# programming.net
KiCad netlist of a schematic drawn in Altium Designer
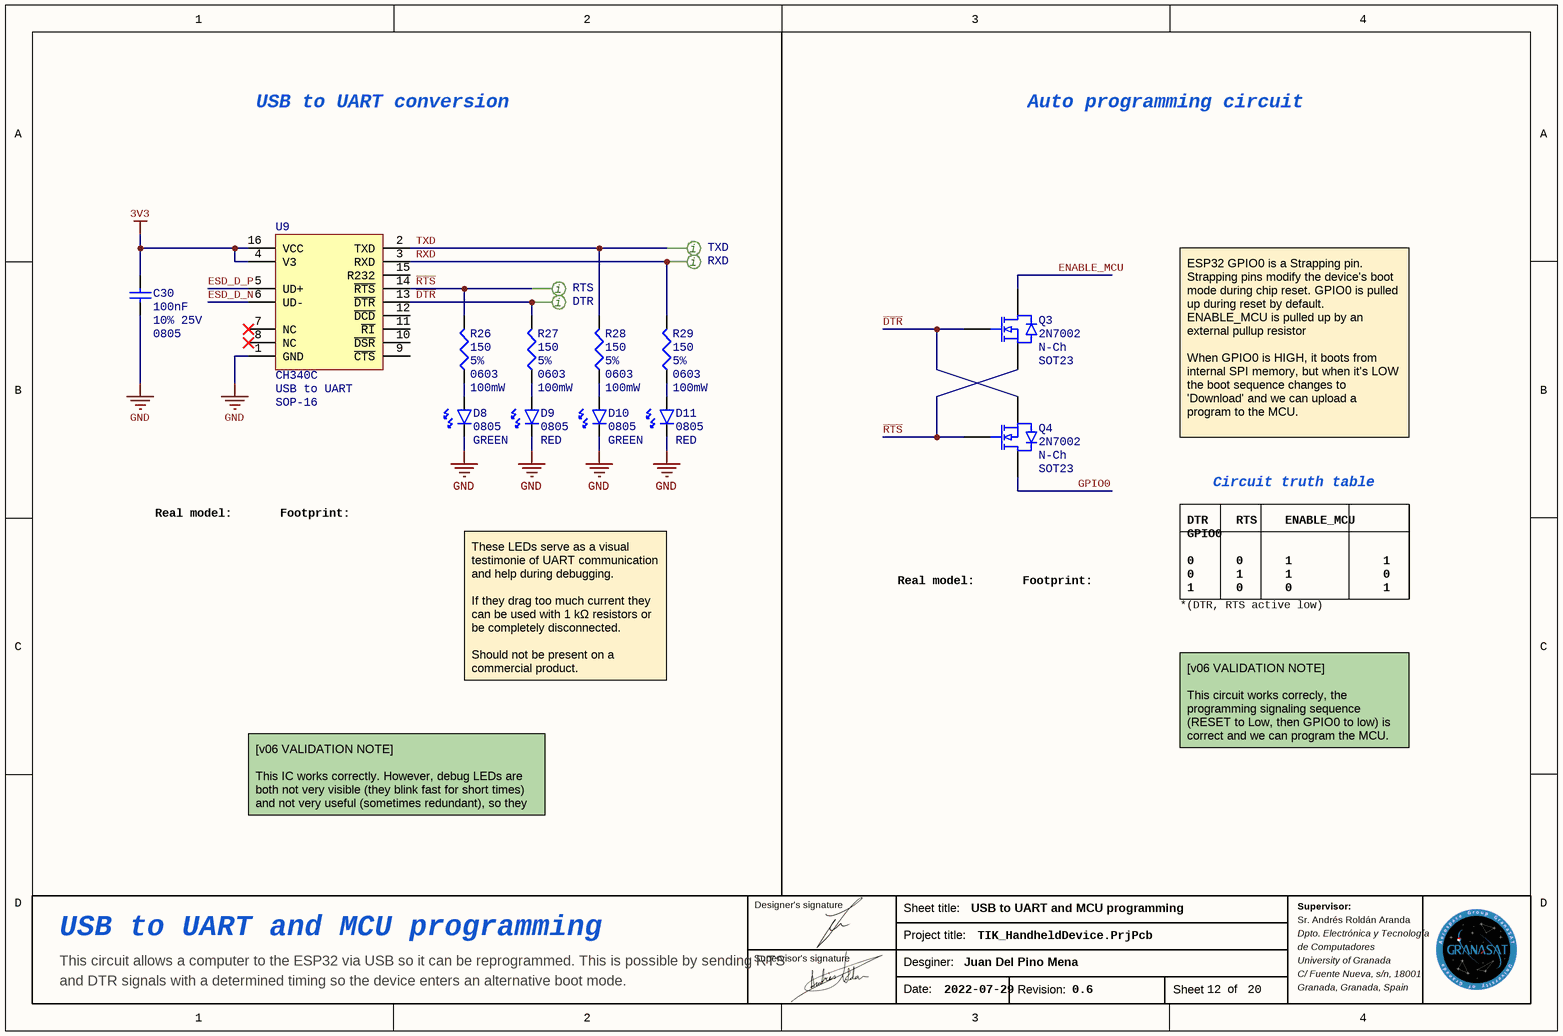
[diagram p0: programming.SchDoc]

(export (version "E")
  (design (tool "Eeschema 10.0.6"))
  (components
    (comp (ref "C30")
      (value "100nF")
      (footprint "CAP 0805_2012")
      (description "Ceramic cap size 0805")
      (fields
        (field (name "TOLERANCE") "10% 25V")
        (field (name "PACKAGEDESCRIPTION") "0805")
        (field (name "Comment") "Cap_cer_0805")
      )
      (libsource (lib "tik_handheld_schlib") (part "Cap_cer_0805_100nF_10%"))
    )
    (comp (ref "D8")
      (value "Diode LED_G_0805")
      (footprint "LED 0805_2012 GREEN")
      (description "Low power LED color Green")
      (fields (field (name "PACKAGEDESCRIPTION") "0805") (field (name "TYPE") "GREEN"))
      (libsource (lib "tik_handheld_schlib") (part "Diode LED_G_0805"))
    )
    (comp (ref "D9")
      (value "Diode LED_R_0805")
      (footprint "LED 0805_2012 RED")
      (description "Low power LED color Red")
      (fields (field (name "PACKAGEDESCRIPTION") "0805") (field (name "TYPE") "RED"))
      (libsource (lib "tik_handheld_schlib") (part "Diode LED_R_0805"))
    )
    (comp (ref "D10")
      (value "Diode LED_G_0805")
      (footprint "LED 0805_2012 GREEN")
      (description "Low power LED color Green")
      (fields (field (name "PACKAGEDESCRIPTION") "0805") (field (name "TYPE") "GREEN"))
      (libsource (lib "tik_handheld_schlib") (part "Diode LED_G_0805"))
    )
    (comp (ref "D11")
      (value "Diode LED_R_0805")
      (footprint "LED 0805_2012 RED")
      (description "Low power LED color Red")
      (fields (field (name "PACKAGEDESCRIPTION") "0805") (field (name "TYPE") "RED"))
      (libsource (lib "tik_handheld_schlib") (part "Diode LED_R_0805"))
    )
    (comp (ref "DTR")
      (value "Test Point Pad dual sided")
      (footprint "TEST POINT PAD")
      (description "Test point - PCB Pad dual sided")
      (libsource (lib "tik_handheld_schlib") (part "Test Point Pad dual sided"))
    )
    (comp (ref "Q3")
      (value "NMOS 2N7002")
      (footprint "SOT-23-3 TO-236AB 2N7002")
      (fields
        (field (name "PART") "2N7002")
        (field (name "TYPE") "N-Ch")
        (field (name "PACKAGEDESCRIPTION") "SOT23")
      )
      (libsource (lib "tik_handheld_schlib") (part "NMOS 2N7002"))
    )
    (comp (ref "Q4")
      (value "NMOS 2N7002")
      (footprint "SOT-23-3 TO-236AB 2N7002")
      (fields
        (field (name "PART") "2N7002")
        (field (name "TYPE") "N-Ch")
        (field (name "PACKAGEDESCRIPTION") "SOT23")
      )
      (libsource (lib "tik_handheld_schlib") (part "NMOS 2N7002"))
    )
    (comp (ref "R26")
      (value "150")
      (footprint "RES 0603_1608")
      (description "Res size 0603 SMD mounting, low power")
      (fields
        (field (name "TOLERANCE") "5%")
        (field (name "PACKAGEDESCRIPTION") "0603")
        (field (name "POWERDISIPATED") "100mW")
        (field (name "Comment") "Res_0603_150_5%_100mW")
      )
      (libsource (lib "tik_handheld_schlib") (part "Res_0603_150_5%_100mW"))
    )
    (comp (ref "R27")
      (value "150")
      (footprint "RES 0603_1608")
      (description "Res size 0603 SMD mounting, low power")
      (fields
        (field (name "TOLERANCE") "5%")
        (field (name "PACKAGEDESCRIPTION") "0603")
        (field (name "POWERDISIPATED") "100mW")
        (field (name "Comment") "Res_0603_150_5%_100mW")
      )
      (libsource (lib "tik_handheld_schlib") (part "Res_0603_150_5%_100mW"))
    )
    (comp (ref "R28")
      (value "150")
      (footprint "RES 0603_1608")
      (description "Res size 0603 SMD mounting, low power")
      (fields
        (field (name "TOLERANCE") "5%")
        (field (name "PACKAGEDESCRIPTION") "0603")
        (field (name "POWERDISIPATED") "100mW")
        (field (name "Comment") "Res_0603_150_5%_100mW")
      )
      (libsource (lib "tik_handheld_schlib") (part "Res_0603_150_5%_100mW"))
    )
    (comp (ref "R29")
      (value "150")
      (footprint "RES 0603_1608")
      (description "Res size 0603 SMD mounting, low power")
      (fields
        (field (name "TOLERANCE") "5%")
        (field (name "PACKAGEDESCRIPTION") "0603")
        (field (name "POWERDISIPATED") "100mW")
        (field (name "Comment") "Res_0603_150_5%_100mW")
      )
      (libsource (lib "tik_handheld_schlib") (part "Res_0603_150_5%_100mW"))
    )
    (comp (ref "RTS")
      (value "Test Point Pad dual sided")
      (footprint "TEST POINT PAD")
      (description "Test point - PCB Pad dual sided")
      (libsource (lib "tik_handheld_schlib") (part "Test Point Pad dual sided"))
    )
    (comp (ref "RXD")
      (value "Test Point Pad dual sided")
      (footprint "TEST POINT PAD")
      (description "Test point - PCB Pad dual sided")
      (libsource (lib "tik_handheld_schlib") (part "Test Point Pad dual sided"))
    )
    (comp (ref "TXD")
      (value "Test Point Pad dual sided")
      (footprint "TEST POINT PAD")
      (description "Test point - PCB Pad dual sided")
      (libsource (lib "tik_handheld_schlib") (part "Test Point Pad dual sided"))
    )
    (comp (ref "U9")
      (value "CH340C")
      (footprint "SSOP-16 150mil CH340C")
      (description "USB to serial chip CH340C, integrated oscillator.")
      (fields
        (field (name "PART") "CH340C")
        (field (name "TYPE") "USB to UART")
        (field (name "PACKAGEDESCRIPTION") "SOP-16")
      )
      (libsource (lib "tik_handheld_schlib") (part "IC CH340C usb to ttl"))
    )
  )
  (nets
    (net (code "1") (name "/ENABLE_MCU") (class "Default")
      (node (ref "Q3") (pin "3") (pinfunction "D_3") (pintype "passive"))
    )
    (net (code "2") (name "/ESD_D_N") (class "Default")
      (node (ref "U9") (pin "6") (pinfunction "UD-_6") (pintype "power_in"))
    )
    (net (code "3") (name "/ESD_D_P") (class "Default")
      (node (ref "U9") (pin "5") (pinfunction "UD+_5") (pintype "open_collector"))
    )
    (net (code "4") (name "/GPIO0") (class "Default")
      (node (ref "Q4") (pin "3") (pinfunction "D_3") (pintype "passive"))
    )
    (net (code "5") (name "/RXD") (class "Default")
      (node (ref "R29") (pin "2") (pinfunction "2_2") (pintype "passive"))
      (node (ref "RXD") (pin "1") (pinfunction "1_1") (pintype "passive"))
      (node (ref "U9") (pin "3") (pinfunction "RXD_3") (pintype "open_collector"))
    )
    (net (code "6") (name "/TXD") (class "Default")
      (node (ref "R28") (pin "2") (pinfunction "2_2") (pintype "passive"))
      (node (ref "TXD") (pin "1") (pinfunction "1_1") (pintype "passive"))
      (node (ref "U9") (pin "2") (pinfunction "TXD_2") (pintype "open_collector"))
    )
    (net (code "7") (name "/~{DTR}") (class "Default")
      (node (ref "DTR") (pin "1") (pinfunction "1_1") (pintype "passive"))
      (node (ref "Q3") (pin "1") (pinfunction "G_1") (pintype "passive"))
      (node (ref "Q4") (pin "2") (pinfunction "S_2") (pintype "passive"))
      (node (ref "R27") (pin "2") (pinfunction "2_2") (pintype "passive"))
      (node (ref "U9") (pin "13") (pinfunction "~{DTR}_13") (pintype "open_collector"))
    )
    (net (code "8") (name "/~{RTS}") (class "Default")
      (node (ref "Q3") (pin "2") (pinfunction "S_2") (pintype "passive"))
      (node (ref "Q4") (pin "1") (pinfunction "G_1") (pintype "passive"))
      (node (ref "R26") (pin "2") (pinfunction "2_2") (pintype "passive"))
      (node (ref "RTS") (pin "1") (pinfunction "1_1") (pintype "passive"))
      (node (ref "U9") (pin "14") (pinfunction "~{RTS}_14") (pintype "open_collector"))
    )
    (net (code "9") (name "3V3") (class "Default")
      (node (ref "C30") (pin "2") (pinfunction "2_2") (pintype "passive"))
      (node (ref "U9") (pin "16") (pinfunction "VCC_16") (pintype "power_in"))
      (node (ref "U9") (pin "4") (pinfunction "V3_4") (pintype "power_in"))
    )
    (net (code "10") (name "GND") (class "Default")
      (node (ref "C30") (pin "1") (pinfunction "1_1") (pintype "passive"))
      (node (ref "D10") (pin "2") (pinfunction "2_2") (pintype "passive"))
      (node (ref "D11") (pin "2") (pinfunction "2_2") (pintype "passive"))
      (node (ref "D8") (pin "2") (pinfunction "2_2") (pintype "passive"))
      (node (ref "D9") (pin "2") (pinfunction "2_2") (pintype "passive"))
      (node (ref "U9") (pin "1") (pinfunction "GND_1") (pintype "power_in"))
    )
    (net (code "11") (name "Net-(D8-Pad1)") (class "Default")
      (node (ref "D8") (pin "1") (pinfunction "1_1") (pintype "passive"))
      (node (ref "R26") (pin "1") (pinfunction "1_1") (pintype "passive"))
    )
    (net (code "12") (name "Net-(D9-Pad1)") (class "Default")
      (node (ref "D9") (pin "1") (pinfunction "1_1") (pintype "passive"))
      (node (ref "R27") (pin "1") (pinfunction "1_1") (pintype "passive"))
    )
    (net (code "13") (name "Net-(D10-Pad1)") (class "Default")
      (node (ref "D10") (pin "1") (pinfunction "1_1") (pintype "passive"))
      (node (ref "R28") (pin "1") (pinfunction "1_1") (pintype "passive"))
    )
    (net (code "14") (name "Net-(D11-Pad1)") (class "Default")
      (node (ref "D11") (pin "1") (pinfunction "1_1") (pintype "passive"))
      (node (ref "R29") (pin "1") (pinfunction "1_1") (pintype "passive"))
    )
    (net (code "15") (name "unconnected-(U9-NC-Pad7)") (class "Default")
      (node (ref "U9") (pin "7") (pinfunction "NC_7") (pintype "power_in+no_connect"))
    )
    (net (code "16") (name "unconnected-(U9-NC-Pad8)") (class "Default")
      (node (ref "U9") (pin "8") (pinfunction "NC_8") (pintype "open_collector+no_connect"))
    )
    (net (code "17") (name "unconnected-(U9-R232-Pad15)") (class "Default")
      (node (ref "U9") (pin "15") (pinfunction "R232_15") (pintype "open_collector"))
    )
    (net (code "18") (name "unconnected-(U9-~{CTS}-Pad9)") (class "Default")
      (node (ref "U9") (pin "9") (pinfunction "~{CTS}_9") (pintype "open_collector"))
    )
    (net (code "19") (name "unconnected-(U9-~{DCD}-Pad12)") (class "Default")
      (node (ref "U9") (pin "12") (pinfunction "~{DCD}_12") (pintype "open_collector"))
    )
    (net (code "20") (name "unconnected-(U9-~{DSR}-Pad10)") (class "Default")
      (node (ref "U9") (pin "10") (pinfunction "~{DSR}_10") (pintype "open_collector"))
    )
    (net (code "21") (name "unconnected-(U9-~{RI}-Pad11)") (class "Default")
      (node (ref "U9") (pin "11") (pinfunction "~{RI}_11") (pintype "open_collector"))
    )
  )
)
